# asserv_v2.net
KiCad netlist of a schematic drawn in EAGLE
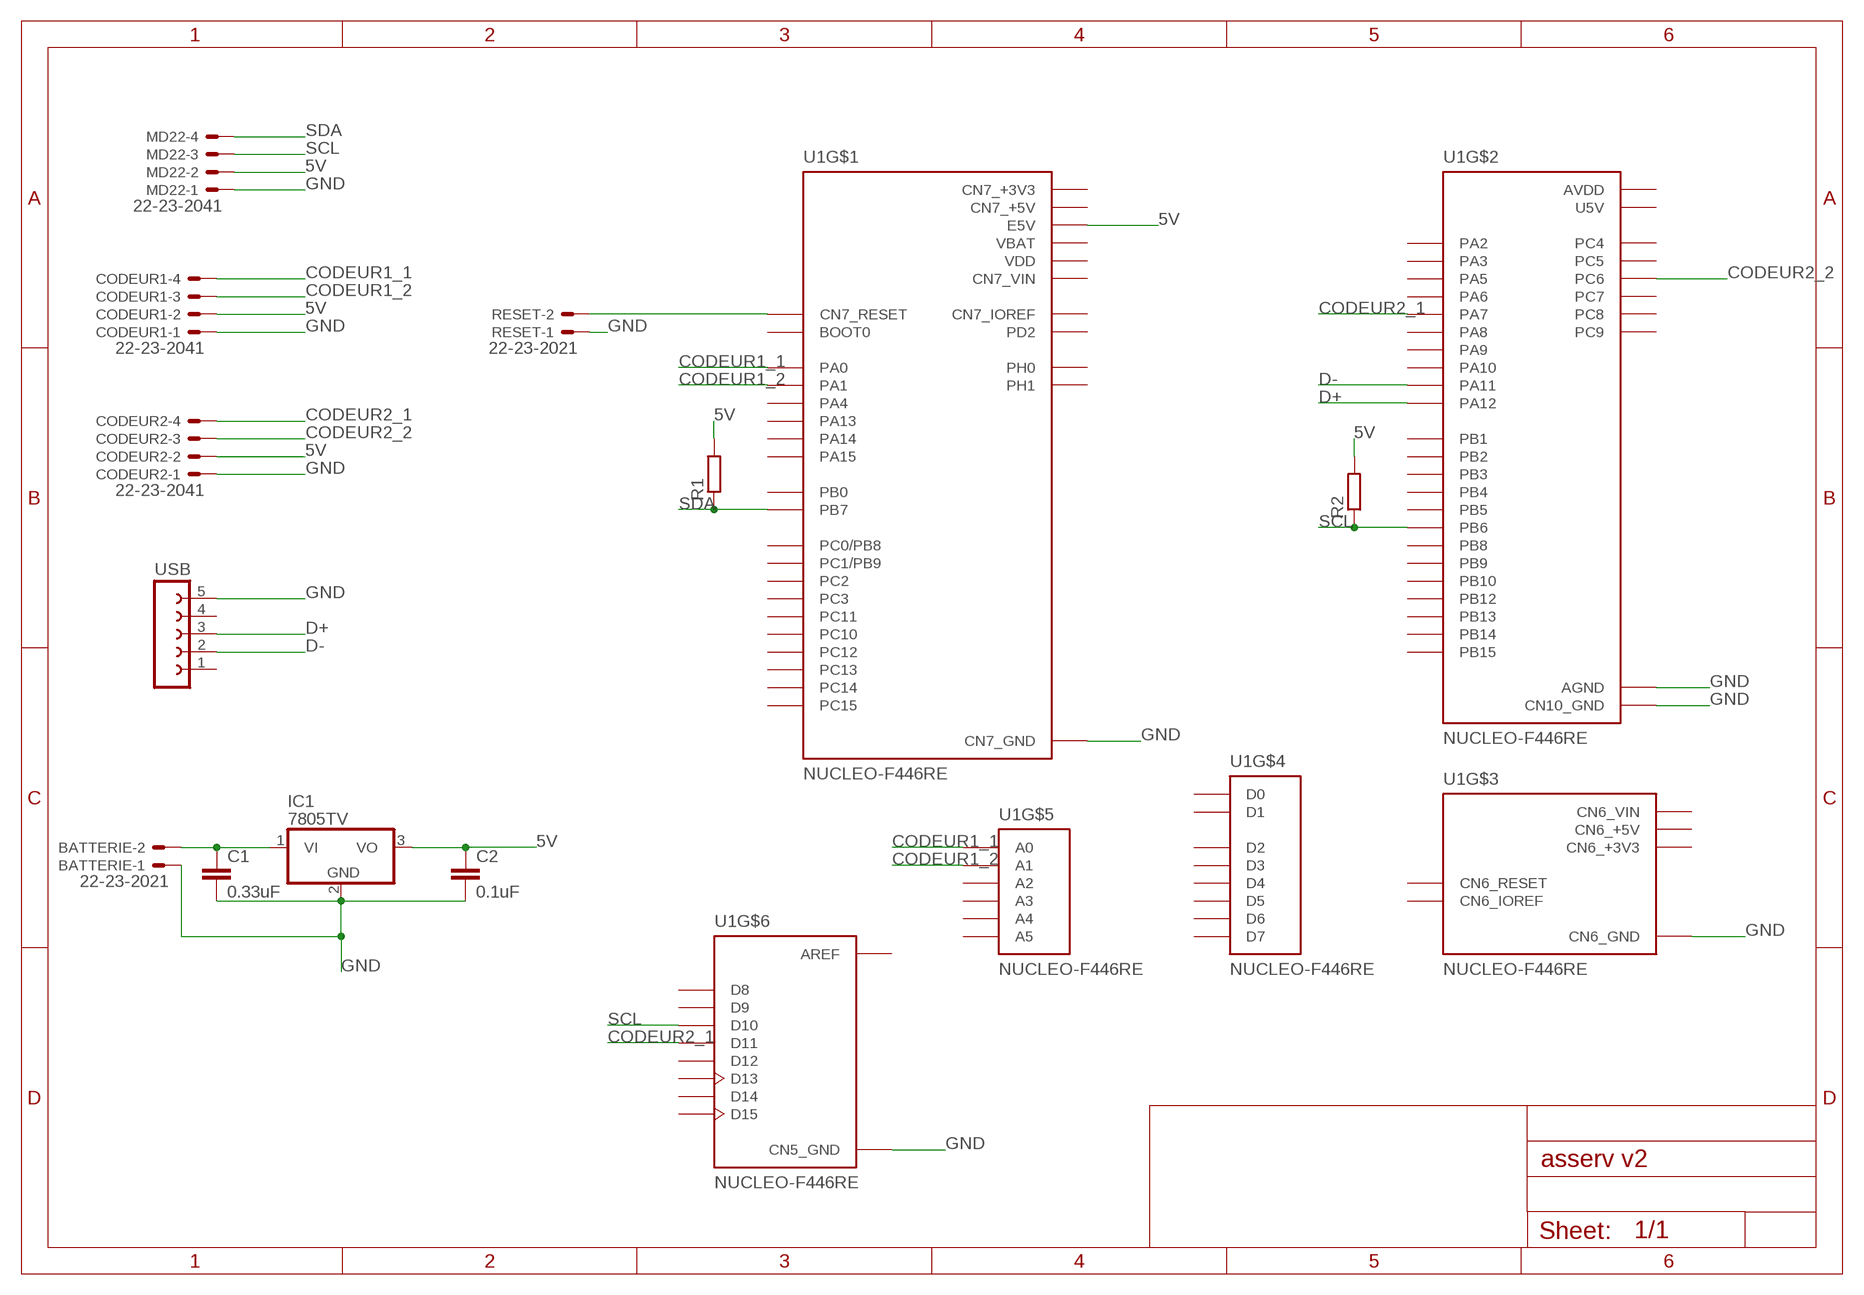
[diagram p0: schematic, sheet 1]

(export (version "E")
  (design (tool "Eeschema 10.0.6"))
  (components
    (comp (ref "BATTERIE")
      (value "22-23-2021")
      (footprint "eagle-import:22-23-2021")
      (fields (field (name "MF") "MOLEX"))
      (libsource (lib "eagle-import") (part "22-23-2021"))
    )
    (comp (ref "C1")
      (value "0.33uF")
      (footprint "eagle-import:C5B2.5")
      (libsource (lib "eagle-import") (part "C5/2.5"))
    )
    (comp (ref "C2")
      (value "0.1uF")
      (footprint "eagle-import:C5B2.5")
      (libsource (lib "eagle-import") (part "C5/2.5"))
    )
    (comp (ref "CODEUR1")
      (value "22-23-2041")
      (footprint "eagle-import:22-23-2041")
      (fields (field (name "MF") "MOLEX"))
      (libsource (lib "eagle-import") (part "22-23-2041"))
    )
    (comp (ref "CODEUR2")
      (value "22-23-2041")
      (footprint "eagle-import:22-23-2041")
      (fields (field (name "MF") "MOLEX"))
      (libsource (lib "eagle-import") (part "22-23-2041"))
    )
    (comp (ref "IC1")
      (value "7805TV")
      (footprint "eagle-import:TO220V")
      (libsource (lib "eagle-import") (part "78TV05"))
    )
    (comp (ref "MD22")
      (value "22-23-2041")
      (footprint "eagle-import:22-23-2041")
      (fields (field (name "MF") "MOLEX"))
      (libsource (lib "eagle-import") (part "22-23-2041"))
    )
    (comp (ref "R1")
      (value "R-EU_0204/7")
      (footprint "eagle-import:0204_7")
      (libsource (lib "eagle-import") (part "R-EU_0204/7"))
    )
    (comp (ref "R2")
      (value "R-EU_0204/7")
      (footprint "eagle-import:0204_7")
      (libsource (lib "eagle-import") (part "R-EU_0204/7"))
    )
    (comp (ref "RESET")
      (value "22-23-2021")
      (footprint "eagle-import:22-23-2021")
      (fields (field (name "MF") "MOLEX"))
      (libsource (lib "eagle-import") (part "22-23-2021"))
    )
    (comp (ref "U1")
      (value "NUCLEO-F446RE")
      (footprint "eagle-import:MODULE_NUCLEO-F446RE")
      (fields
        (field (name "MF") "STMicroelectronics")
        (field (name "MF_1") "STMICROELECTRONICS")
        (field (name "SPICEPREFIX") "X")
        (field (name "MPN") "NUCLEO-F446RE")
        (field (name "OC_FARNELL") "2491978")
      )
      (libsource (lib "eagle-import") (part "NUCLEO-F446RE"))
    )
    (comp (ref "USB")
      (value "FE05-1")
      (footprint "eagle-import:FE05-1")
      (libsource (lib "eagle-import") (part "FE05-1"))
    )
  )
  (nets
    (net (code "1") (name "/5V") (class "Default")
      (node (ref "C2") (pin "1") (pinfunction "1_1") (pintype "passive"))
      (node (ref "CODEUR1") (pin "2") (pinfunction "S_2") (pintype "passive"))
      (node (ref "CODEUR2") (pin "2") (pinfunction "S_2") (pintype "passive"))
      (node (ref "IC1") (pin "3") (pinfunction "VO_3") (pintype "passive"))
      (node (ref "MD22") (pin "2") (pinfunction "S_2") (pintype "passive"))
      (node (ref "R1") (pin "2") (pinfunction "2_2") (pintype "passive"))
      (node (ref "R2") (pin "2") (pinfunction "2_2") (pintype "passive"))
      (node (ref "U1") (pin "CN7_6") (pinfunction "E5V_CN7_6") (pintype "power_in"))
    )
    (net (code "2") (name "/AREF") (class "Default")
      (node (ref "U1") (pin "CN5_8") (pinfunction "AREF_CN5_8") (pintype "power_in"))
    )
    (net (code "3") (name "/AVDD") (class "Default")
      (node (ref "U1") (pin "CN10_7") (pinfunction "AVDD_CN10_7") (pintype "power_in"))
    )
    (net (code "4") (name "/CN6_+3V3") (class "Default")
      (node (ref "U1") (pin "CN6_4") (pinfunction "CN6_+3V3_CN6_4") (pintype "power_in"))
    )
    (net (code "5") (name "/CN6_+5V") (class "Default")
      (node (ref "U1") (pin "CN6_5") (pinfunction "CN6_+5V_CN6_5") (pintype "power_in"))
    )
    (net (code "6") (name "/CN6_VIN") (class "Default")
      (node (ref "U1") (pin "CN6_8") (pinfunction "CN6_VIN_CN6_8") (pintype "power_in"))
    )
    (net (code "7") (name "/CN7_+3V3") (class "Default")
      (node (ref "U1") (pin "CN7_16") (pinfunction "CN7_+3V3_CN7_16") (pintype "power_in"))
    )
    (net (code "8") (name "/CN7_+5V") (class "Default")
      (node (ref "U1") (pin "CN7_18") (pinfunction "CN7_+5V_CN7_18") (pintype "power_in"))
    )
    (net (code "9") (name "/CN7_VIN") (class "Default")
      (node (ref "U1") (pin "CN7_24") (pinfunction "CN7_VIN_CN7_24") (pintype "power_in"))
    )
    (net (code "10") (name "/CODEUR1_1") (class "Default")
      (node (ref "CODEUR1") (pin "4") (pinfunction "S_4") (pintype "passive"))
      (node (ref "U1") (pin "CN7_28") (pinfunction "PA0_CN7_28") (pintype "bidirectional"))
      (node (ref "U1") (pin "CN8_1") (pinfunction "A0_CN8_1") (pintype "input"))
    )
    (net (code "11") (name "/CODEUR1_2") (class "Default")
      (node (ref "CODEUR1") (pin "3") (pinfunction "S_3") (pintype "passive"))
      (node (ref "U1") (pin "CN7_30") (pinfunction "PA1_CN7_30") (pintype "bidirectional"))
      (node (ref "U1") (pin "CN8_2") (pinfunction "A1_CN8_2") (pintype "input"))
    )
    (net (code "12") (name "/CODEUR2_1") (class "Default")
      (node (ref "CODEUR2") (pin "4") (pinfunction "S_4") (pintype "passive"))
      (node (ref "U1") (pin "CN10_15") (pinfunction "PA7_CN10_15") (pintype "bidirectional"))
      (node (ref "U1") (pin "CN5_4") (pinfunction "D11_CN5_4") (pintype "bidirectional"))
    )
    (net (code "13") (name "/CODEUR2_2") (class "Default")
      (node (ref "CODEUR2") (pin "3") (pinfunction "S_3") (pintype "passive"))
      (node (ref "U1") (pin "CN10_4") (pinfunction "PC6_CN10_4") (pintype "bidirectional"))
    )
    (net (code "14") (name "/D+") (class "Default")
      (node (ref "U1") (pin "CN10_12") (pinfunction "PA12_CN10_12") (pintype "bidirectional"))
      (node (ref "USB") (pin "3") (pinfunction "3_3") (pintype "passive"))
    )
    (net (code "15") (name "/D-") (class "Default")
      (node (ref "U1") (pin "CN10_14") (pinfunction "PA11_CN10_14") (pintype "bidirectional"))
      (node (ref "USB") (pin "2") (pinfunction "2_2") (pintype "passive"))
    )
    (net (code "16") (name "/GND") (class "Default")
      (node (ref "BATTERIE") (pin "1") (pinfunction "S_1") (pintype "passive"))
      (node (ref "C1") (pin "2") (pinfunction "2_2") (pintype "passive"))
      (node (ref "C2") (pin "2") (pinfunction "2_2") (pintype "passive"))
      (node (ref "CODEUR1") (pin "1") (pinfunction "S_1") (pintype "passive"))
      (node (ref "CODEUR2") (pin "1") (pinfunction "S_1") (pintype "passive"))
      (node (ref "IC1") (pin "2") (pinfunction "GND_2") (pintype "passive"))
      (node (ref "MD22") (pin "1") (pinfunction "S_1") (pintype "passive"))
      (node (ref "RESET") (pin "1") (pinfunction "S_1") (pintype "passive"))
      (node (ref "U1") (pin "CN10_20") (pinfunction "CN10_GND_CN10_20") (pintype "power_in"))
      (node (ref "U1") (pin "CN10_32") (pinfunction "AGND_CN10_32") (pintype "power_in"))
      (node (ref "U1") (pin "CN10_9") (pinfunction "CN10_GND_CN10_9") (pintype "power_in"))
      (node (ref "U1") (pin "CN5_7") (pinfunction "CN5_GND_CN5_7") (pintype "power_in"))
      (node (ref "U1") (pin "CN6_6") (pinfunction "CN6_GND_CN6_6") (pintype "power_in"))
      (node (ref "U1") (pin "CN6_7") (pinfunction "CN6_GND_CN6_7") (pintype "power_in"))
      (node (ref "U1") (pin "CN7_19") (pinfunction "CN7_GND_CN7_19") (pintype "power_in"))
      (node (ref "U1") (pin "CN7_20") (pinfunction "CN7_GND_CN7_20") (pintype "power_in"))
      (node (ref "U1") (pin "CN7_22") (pinfunction "CN7_GND_CN7_22") (pintype "power_in"))
      (node (ref "U1") (pin "CN7_8") (pinfunction "CN7_GND_CN7_8") (pintype "power_in"))
      (node (ref "USB") (pin "5") (pinfunction "5_5") (pintype "passive"))
    )
    (net (code "17") (name "/SCL") (class "Default")
      (node (ref "MD22") (pin "3") (pinfunction "S_3") (pintype "passive"))
      (node (ref "R2") (pin "1") (pinfunction "1_1") (pintype "passive"))
      (node (ref "U1") (pin "CN10_17") (pinfunction "PB6_CN10_17") (pintype "bidirectional"))
      (node (ref "U1") (pin "CN5_3") (pinfunction "D10_CN5_3") (pintype "bidirectional"))
    )
    (net (code "18") (name "/SDA") (class "Default")
      (node (ref "MD22") (pin "4") (pinfunction "S_4") (pintype "passive"))
      (node (ref "R1") (pin "1") (pinfunction "1_1") (pintype "passive"))
      (node (ref "U1") (pin "CN7_21") (pinfunction "PB7_CN7_21") (pintype "bidirectional"))
    )
    (net (code "19") (name "/U5V") (class "Default")
      (node (ref "U1") (pin "CN10_8") (pinfunction "U5V_CN10_8") (pintype "power_in"))
    )
    (net (code "20") (name "/VBAT") (class "Default")
      (node (ref "U1") (pin "CN7_33") (pinfunction "VBAT_CN7_33") (pintype "power_in"))
    )
    (net (code "21") (name "/VDD") (class "Default")
      (node (ref "U1") (pin "CN7_5") (pinfunction "VDD_CN7_5") (pintype "power_in"))
    )
    (net (code "22") (name "Net-(BATTERIEB-S)") (class "Default")
      (node (ref "BATTERIE") (pin "2") (pinfunction "S_2") (pintype "passive"))
      (node (ref "C1") (pin "1") (pinfunction "1_1") (pintype "passive"))
      (node (ref "IC1") (pin "1") (pinfunction "VI_1") (pintype "input"))
    )
    (net (code "23") (name "Net-(RESETB-S)") (class "Default")
      (node (ref "RESET") (pin "2") (pinfunction "S_2") (pintype "passive"))
      (node (ref "U1") (pin "CN7_14") (pinfunction "CN7_RESET_CN7_14") (pintype "bidirectional"))
    )
    (net (code "24") (name "unconnected-(U1A-BOOT0-PadCN7_7)") (class "Default")
      (node (ref "U1") (pin "CN7_7") (pinfunction "BOOT0_CN7_7") (pintype "bidirectional"))
    )
    (net (code "25") (name "unconnected-(U1A-CN7_IOREF-PadCN7_12)") (class "Default")
      (node (ref "U1") (pin "CN7_12") (pinfunction "CN7_IOREF_CN7_12") (pintype "bidirectional"))
    )
    (net (code "26") (name "unconnected-(U1A-PA4-PadCN7_32)") (class "Default")
      (node (ref "U1") (pin "CN7_32") (pinfunction "PA4_CN7_32") (pintype "bidirectional"))
    )
    (net (code "27") (name "unconnected-(U1A-PA13-PadCN7_13)") (class "Default")
      (node (ref "U1") (pin "CN7_13") (pinfunction "PA13_CN7_13") (pintype "bidirectional"))
    )
    (net (code "28") (name "unconnected-(U1A-PA14-PadCN7_15)") (class "Default")
      (node (ref "U1") (pin "CN7_15") (pinfunction "PA14_CN7_15") (pintype "bidirectional"))
    )
    (net (code "29") (name "unconnected-(U1A-PA15-PadCN7_17)") (class "Default")
      (node (ref "U1") (pin "CN7_17") (pinfunction "PA15_CN7_17") (pintype "bidirectional"))
    )
    (net (code "30") (name "unconnected-(U1A-PB0-PadCN7_34)") (class "Default")
      (node (ref "U1") (pin "CN7_34") (pinfunction "PB0_CN7_34") (pintype "bidirectional"))
    )
    (net (code "31") (name "unconnected-(U1A-PC0{slash}PB8-PadCN7_38)") (class "Default")
      (node (ref "U1") (pin "CN7_38") (pinfunction "PC0/PB8_CN7_38") (pintype "bidirectional"))
    )
    (net (code "32") (name "unconnected-(U1A-PC1{slash}PB9-PadCN7_36)") (class "Default")
      (node (ref "U1") (pin "CN7_36") (pinfunction "PC1/PB9_CN7_36") (pintype "bidirectional"))
    )
    (net (code "33") (name "unconnected-(U1A-PC2-PadCN7_35)") (class "Default")
      (node (ref "U1") (pin "CN7_35") (pinfunction "PC2_CN7_35") (pintype "bidirectional"))
    )
    (net (code "34") (name "unconnected-(U1A-PC3-PadCN7_37)") (class "Default")
      (node (ref "U1") (pin "CN7_37") (pinfunction "PC3_CN7_37") (pintype "bidirectional"))
    )
    (net (code "35") (name "unconnected-(U1A-PC10-PadCN7_1)") (class "Default")
      (node (ref "U1") (pin "CN7_1") (pinfunction "PC10_CN7_1") (pintype "bidirectional"))
    )
    (net (code "36") (name "unconnected-(U1A-PC11-PadCN7_2)") (class "Default")
      (node (ref "U1") (pin "CN7_2") (pinfunction "PC11_CN7_2") (pintype "bidirectional"))
    )
    (net (code "37") (name "unconnected-(U1A-PC12-PadCN7_3)") (class "Default")
      (node (ref "U1") (pin "CN7_3") (pinfunction "PC12_CN7_3") (pintype "bidirectional"))
    )
    (net (code "38") (name "unconnected-(U1A-PC13-PadCN7_23)") (class "Default")
      (node (ref "U1") (pin "CN7_23") (pinfunction "PC13_CN7_23") (pintype "bidirectional"))
    )
    (net (code "39") (name "unconnected-(U1A-PC14-PadCN7_25)") (class "Default")
      (node (ref "U1") (pin "CN7_25") (pinfunction "PC14_CN7_25") (pintype "bidirectional"))
    )
    (net (code "40") (name "unconnected-(U1A-PC15-PadCN7_27)") (class "Default")
      (node (ref "U1") (pin "CN7_27") (pinfunction "PC15_CN7_27") (pintype "bidirectional"))
    )
    (net (code "41") (name "unconnected-(U1A-PD2-PadCN7_4)") (class "Default")
      (node (ref "U1") (pin "CN7_4") (pinfunction "PD2_CN7_4") (pintype "bidirectional"))
    )
    (net (code "42") (name "unconnected-(U1A-PH0-PadCN7_29)") (class "Default")
      (node (ref "U1") (pin "CN7_29") (pinfunction "PH0_CN7_29") (pintype "bidirectional"))
    )
    (net (code "43") (name "unconnected-(U1A-PH1-PadCN7_31)") (class "Default")
      (node (ref "U1") (pin "CN7_31") (pinfunction "PH1_CN7_31") (pintype "bidirectional"))
    )
    (net (code "44") (name "unconnected-(U1B-PA2-PadCN10_35)") (class "Default")
      (node (ref "U1") (pin "CN10_35") (pinfunction "PA2_CN10_35") (pintype "bidirectional"))
    )
    (net (code "45") (name "unconnected-(U1B-PA3-PadCN10_37)") (class "Default")
      (node (ref "U1") (pin "CN10_37") (pinfunction "PA3_CN10_37") (pintype "bidirectional"))
    )
    (net (code "46") (name "unconnected-(U1B-PA5-PadCN10_11)") (class "Default")
      (node (ref "U1") (pin "CN10_11") (pinfunction "PA5_CN10_11") (pintype "bidirectional"))
    )
    (net (code "47") (name "unconnected-(U1B-PA6-PadCN10_13)") (class "Default")
      (node (ref "U1") (pin "CN10_13") (pinfunction "PA6_CN10_13") (pintype "bidirectional"))
    )
    (net (code "48") (name "unconnected-(U1B-PA8-PadCN10_23)") (class "Default")
      (node (ref "U1") (pin "CN10_23") (pinfunction "PA8_CN10_23") (pintype "bidirectional"))
    )
    (net (code "49") (name "unconnected-(U1B-PA9-PadCN10_21)") (class "Default")
      (node (ref "U1") (pin "CN10_21") (pinfunction "PA9_CN10_21") (pintype "bidirectional"))
    )
    (net (code "50") (name "unconnected-(U1B-PA10-PadCN10_33)") (class "Default")
      (node (ref "U1") (pin "CN10_33") (pinfunction "PA10_CN10_33") (pintype "bidirectional"))
    )
    (net (code "51") (name "unconnected-(U1B-PB1-PadCN10_24)") (class "Default")
      (node (ref "U1") (pin "CN10_24") (pinfunction "PB1_CN10_24") (pintype "bidirectional"))
    )
    (net (code "52") (name "unconnected-(U1B-PB2-PadCN10_22)") (class "Default")
      (node (ref "U1") (pin "CN10_22") (pinfunction "PB2_CN10_22") (pintype "bidirectional"))
    )
    (net (code "53") (name "unconnected-(U1B-PB3-PadCN10_31)") (class "Default")
      (node (ref "U1") (pin "CN10_31") (pinfunction "PB3_CN10_31") (pintype "bidirectional"))
    )
    (net (code "54") (name "unconnected-(U1B-PB4-PadCN10_27)") (class "Default")
      (node (ref "U1") (pin "CN10_27") (pinfunction "PB4_CN10_27") (pintype "bidirectional"))
    )
    (net (code "55") (name "unconnected-(U1B-PB5-PadCN10_29)") (class "Default")
      (node (ref "U1") (pin "CN10_29") (pinfunction "PB5_CN10_29") (pintype "bidirectional"))
    )
    (net (code "56") (name "unconnected-(U1B-PB8-PadCN10_3)") (class "Default")
      (node (ref "U1") (pin "CN10_3") (pinfunction "PB8_CN10_3") (pintype "bidirectional"))
    )
    (net (code "57") (name "unconnected-(U1B-PB9-PadCN10_5)") (class "Default")
      (node (ref "U1") (pin "CN10_5") (pinfunction "PB9_CN10_5") (pintype "bidirectional"))
    )
    (net (code "58") (name "unconnected-(U1B-PB10-PadCN10_25)") (class "Default")
      (node (ref "U1") (pin "CN10_25") (pinfunction "PB10_CN10_25") (pintype "bidirectional"))
    )
    (net (code "59") (name "unconnected-(U1B-PB12-PadCN10_16)") (class "Default")
      (node (ref "U1") (pin "CN10_16") (pinfunction "PB12_CN10_16") (pintype "bidirectional"))
    )
    (net (code "60") (name "unconnected-(U1B-PB13-PadCN10_30)") (class "Default")
      (node (ref "U1") (pin "CN10_30") (pinfunction "PB13_CN10_30") (pintype "bidirectional"))
    )
    (net (code "61") (name "unconnected-(U1B-PB14-PadCN10_28)") (class "Default")
      (node (ref "U1") (pin "CN10_28") (pinfunction "PB14_CN10_28") (pintype "bidirectional"))
    )
    (net (code "62") (name "unconnected-(U1B-PB15-PadCN10_26)") (class "Default")
      (node (ref "U1") (pin "CN10_26") (pinfunction "PB15_CN10_26") (pintype "bidirectional"))
    )
    (net (code "63") (name "unconnected-(U1B-PC4-PadCN10_34)") (class "Default")
      (node (ref "U1") (pin "CN10_34") (pinfunction "PC4_CN10_34") (pintype "bidirectional"))
    )
    (net (code "64") (name "unconnected-(U1B-PC5-PadCN10_6)") (class "Default")
      (node (ref "U1") (pin "CN10_6") (pinfunction "PC5_CN10_6") (pintype "bidirectional"))
    )
    (net (code "65") (name "unconnected-(U1B-PC7-PadCN10_19)") (class "Default")
      (node (ref "U1") (pin "CN10_19") (pinfunction "PC7_CN10_19") (pintype "bidirectional"))
    )
    (net (code "66") (name "unconnected-(U1B-PC8-PadCN10_2)") (class "Default")
      (node (ref "U1") (pin "CN10_2") (pinfunction "PC8_CN10_2") (pintype "bidirectional"))
    )
    (net (code "67") (name "unconnected-(U1B-PC9-PadCN10_1)") (class "Default")
      (node (ref "U1") (pin "CN10_1") (pinfunction "PC9_CN10_1") (pintype "bidirectional"))
    )
    (net (code "68") (name "unconnected-(U1C-CN6_IOREF-PadCN6_2)") (class "Default")
      (node (ref "U1") (pin "CN6_2") (pinfunction "CN6_IOREF_CN6_2") (pintype "bidirectional"))
    )
    (net (code "69") (name "unconnected-(U1C-CN6_RESET-PadCN6_3)") (class "Default")
      (node (ref "U1") (pin "CN6_3") (pinfunction "CN6_RESET_CN6_3") (pintype "bidirectional"))
    )
    (net (code "70") (name "unconnected-(U1D-D0-PadCN9_1)") (class "Default")
      (node (ref "U1") (pin "CN9_1") (pinfunction "D0_CN9_1") (pintype "input"))
    )
    (net (code "71") (name "unconnected-(U1D-D1-PadCN9_2)") (class "Default")
      (node (ref "U1") (pin "CN9_2") (pinfunction "D1_CN9_2") (pintype "output"))
    )
    (net (code "72") (name "unconnected-(U1D-D2-PadCN9_3)") (class "Default")
      (node (ref "U1") (pin "CN9_3") (pinfunction "D2_CN9_3") (pintype "bidirectional"))
    )
    (net (code "73") (name "unconnected-(U1D-D3-PadCN9_4)") (class "Default")
      (node (ref "U1") (pin "CN9_4") (pinfunction "D3_CN9_4") (pintype "bidirectional"))
    )
    (net (code "74") (name "unconnected-(U1D-D4-PadCN9_5)") (class "Default")
      (node (ref "U1") (pin "CN9_5") (pinfunction "D4_CN9_5") (pintype "bidirectional"))
    )
    (net (code "75") (name "unconnected-(U1D-D5-PadCN9_6)") (class "Default")
      (node (ref "U1") (pin "CN9_6") (pinfunction "D5_CN9_6") (pintype "bidirectional"))
    )
    (net (code "76") (name "unconnected-(U1D-D6-PadCN9_7)") (class "Default")
      (node (ref "U1") (pin "CN9_7") (pinfunction "D6_CN9_7") (pintype "bidirectional"))
    )
    (net (code "77") (name "unconnected-(U1D-D7-PadCN9_8)") (class "Default")
      (node (ref "U1") (pin "CN9_8") (pinfunction "D7_CN9_8") (pintype "bidirectional"))
    )
    (net (code "78") (name "unconnected-(U1E-A2-PadCN8_3)") (class "Default")
      (node (ref "U1") (pin "CN8_3") (pinfunction "A2_CN8_3") (pintype "input"))
    )
    (net (code "79") (name "unconnected-(U1E-A3-PadCN8_4)") (class "Default")
      (node (ref "U1") (pin "CN8_4") (pinfunction "A3_CN8_4") (pintype "input"))
    )
    (net (code "80") (name "unconnected-(U1E-A4-PadCN8_5)") (class "Default")
      (node (ref "U1") (pin "CN8_5") (pinfunction "A4_CN8_5") (pintype "input"))
    )
    (net (code "81") (name "unconnected-(U1E-A5-PadCN8_6)") (class "Default")
      (node (ref "U1") (pin "CN8_6") (pinfunction "A5_CN8_6") (pintype "input"))
    )
    (net (code "82") (name "unconnected-(U1F-D8-PadCN5_1)") (class "Default")
      (node (ref "U1") (pin "CN5_1") (pinfunction "D8_CN5_1") (pintype "bidirectional"))
    )
    (net (code "83") (name "unconnected-(U1F-D9-PadCN5_2)") (class "Default")
      (node (ref "U1") (pin "CN5_2") (pinfunction "D9_CN5_2") (pintype "bidirectional"))
    )
    (net (code "84") (name "unconnected-(U1F-D12-PadCN5_5)") (class "Default")
      (node (ref "U1") (pin "CN5_5") (pinfunction "D12_CN5_5") (pintype "bidirectional"))
    )
    (net (code "85") (name "unconnected-(U1F-D13-PadCN5_6)") (class "Default")
      (node (ref "U1") (pin "CN5_6") (pinfunction "D13_CN5_6") (pintype "bidirectional"))
    )
    (net (code "86") (name "unconnected-(U1F-D14-PadCN5_9)") (class "Default")
      (node (ref "U1") (pin "CN5_9") (pinfunction "D14_CN5_9") (pintype "bidirectional"))
    )
    (net (code "87") (name "unconnected-(U1F-D15-PadCN5_10)") (class "Default")
      (node (ref "U1") (pin "CN5_10") (pinfunction "D15_CN5_10") (pintype "bidirectional"))
    )
    (net (code "88") (name "unconnected-(USB-Pad1)") (class "Default")
      (node (ref "USB") (pin "1") (pinfunction "1_1") (pintype "passive"))
    )
    (net (code "89") (name "unconnected-(USB-Pad4)") (class "Default")
      (node (ref "USB") (pin "4") (pinfunction "4_4") (pintype "passive"))
    )
  )
)
